# b.net
KiCad netlist of a schematic drawn in EAGLE
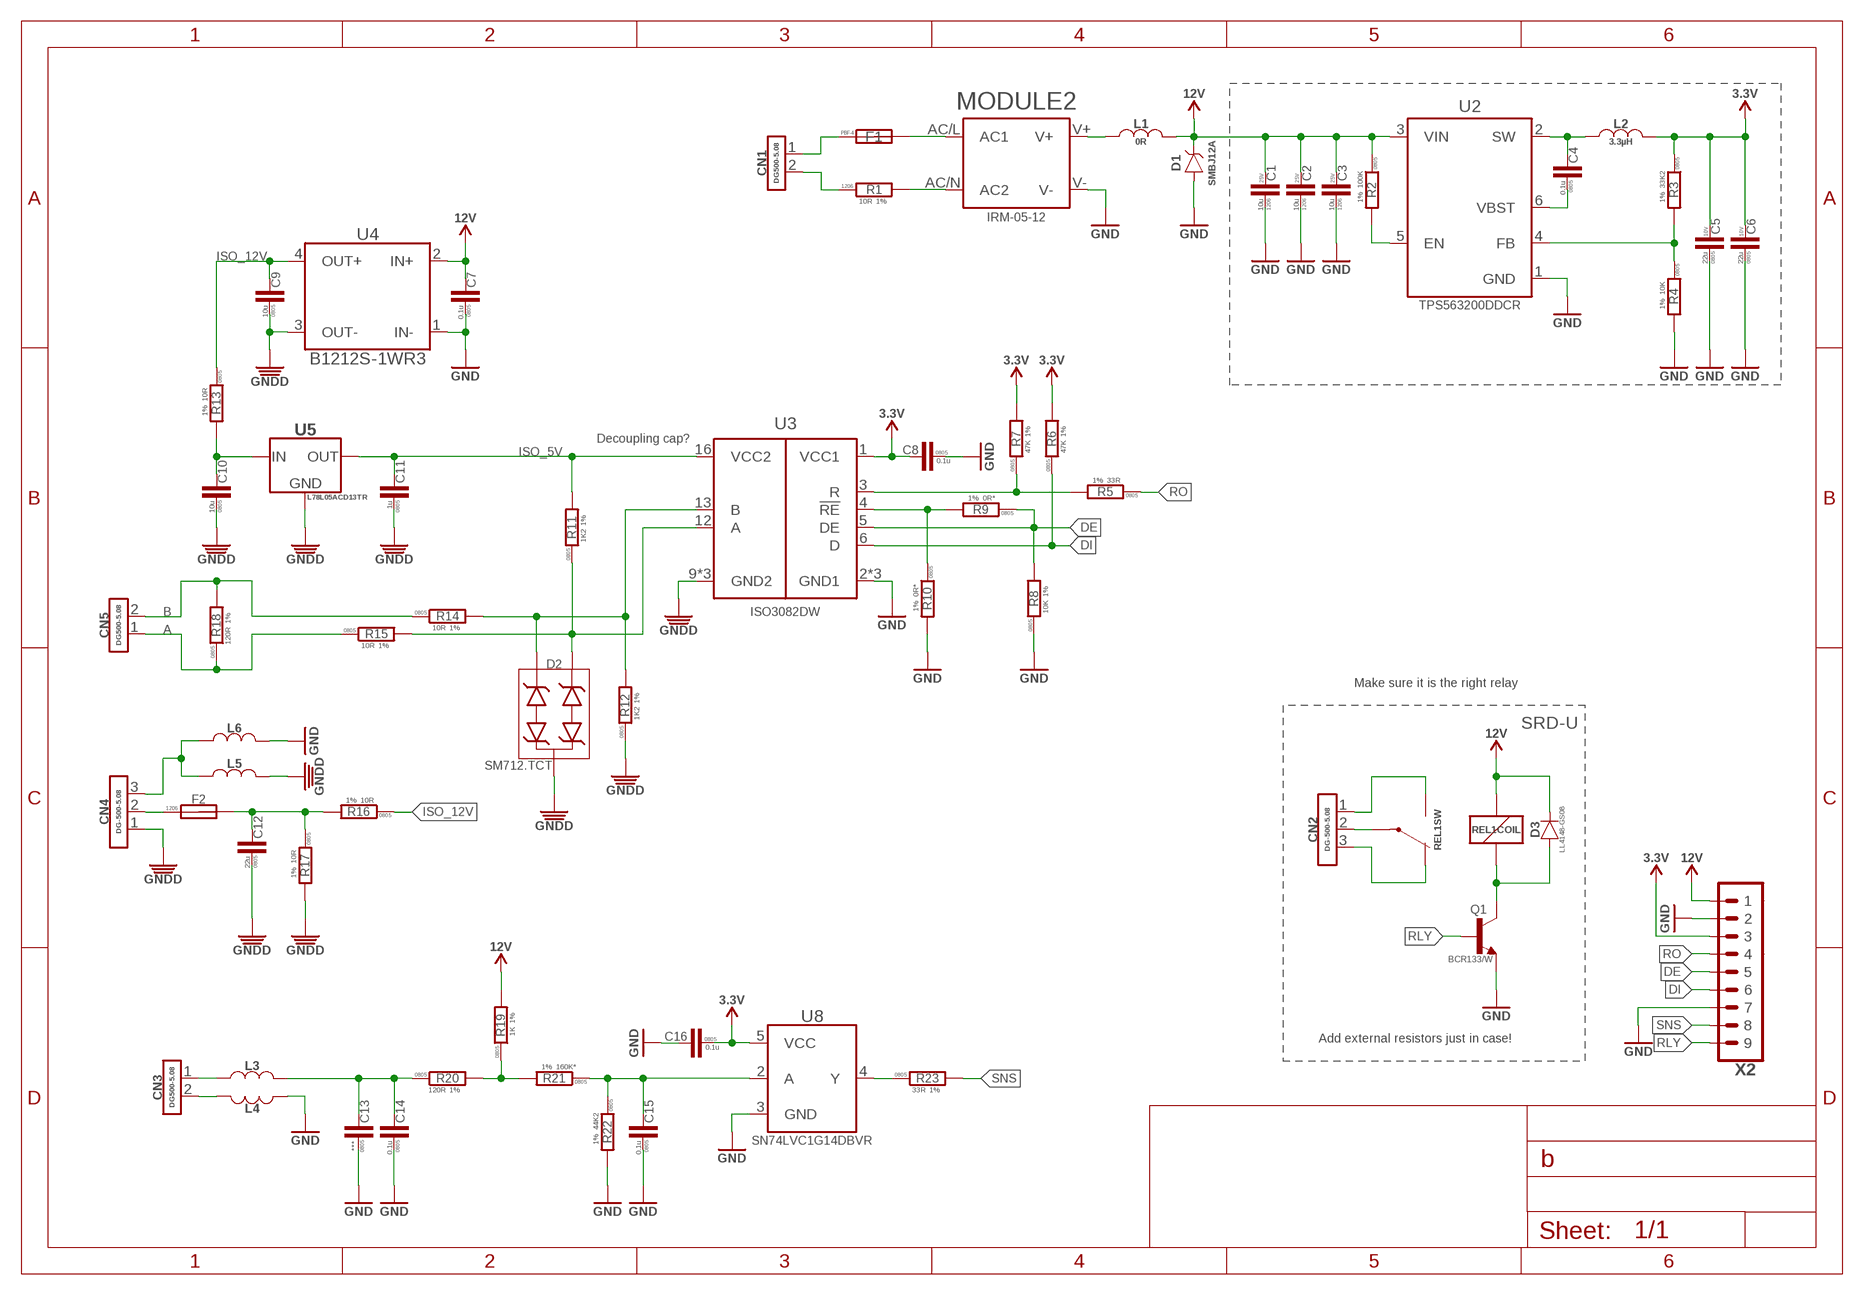
[diagram p0: schematic, sheet 1]

(export (version "E")
  (design (tool "Eeschema 10.0.6"))
  (components
    (comp (ref "C1")
      (value "10u")
      (footprint "eagle-import:C1206")
      (fields (field (name "PACKAGE") "1206") (field (name "VOLTAGE") "25V"))
      (libsource (lib "eagle-import") (part "C-1206"))
    )
    (comp (ref "C2")
      (value "10u")
      (footprint "eagle-import:C1206")
      (fields (field (name "PACKAGE") "1206") (field (name "VOLTAGE") "25V"))
      (libsource (lib "eagle-import") (part "C-1206"))
    )
    (comp (ref "C3")
      (value "10u")
      (footprint "eagle-import:C1206")
      (fields (field (name "PACKAGE") "1206") (field (name "VOLTAGE") "25V"))
      (libsource (lib "eagle-import") (part "C-1206"))
    )
    (comp (ref "C4")
      (value "0.1u")
      (footprint "eagle-import:C0805")
      (fields (field (name "PACKAGE") "0805"))
      (libsource (lib "eagle-import") (part "C-0805"))
    )
    (comp (ref "C5")
      (value "22u")
      (footprint "eagle-import:C0805")
      (fields (field (name "PACKAGE") "0805") (field (name "VOLTAGE") "10V"))
      (libsource (lib "eagle-import") (part "C-0805"))
    )
    (comp (ref "C6")
      (value "22u")
      (footprint "eagle-import:C0805")
      (fields (field (name "PACKAGE") "0805") (field (name "VOLTAGE") "10V"))
      (libsource (lib "eagle-import") (part "C-0805"))
    )
    (comp (ref "C7")
      (value "0.1u")
      (footprint "eagle-import:C0805")
      (fields (field (name "PACKAGE") "0805"))
      (libsource (lib "eagle-import") (part "C-0805"))
    )
    (comp (ref "C8")
      (value "0.1u")
      (footprint "eagle-import:C0805")
      (fields (field (name "PACKAGE") "0805"))
      (libsource (lib "eagle-import") (part "C-0805"))
    )
    (comp (ref "C9")
      (value "10u")
      (footprint "eagle-import:C0805")
      (fields (field (name "PACKAGE") "0805"))
      (libsource (lib "eagle-import") (part "C-0805"))
    )
    (comp (ref "C10")
      (value "10u")
      (footprint "eagle-import:C0805")
      (fields (field (name "PACKAGE") "0805"))
      (libsource (lib "eagle-import") (part "C-0805"))
    )
    (comp (ref "C11")
      (value "1u")
      (footprint "eagle-import:C0805")
      (fields (field (name "PACKAGE") "0805"))
      (libsource (lib "eagle-import") (part "C-0805"))
    )
    (comp (ref "C12")
      (value "22u")
      (footprint "eagle-import:C0805")
      (fields (field (name "PACKAGE") "0805"))
      (libsource (lib "eagle-import") (part "C-0805"))
    )
    (comp (ref "C13")
      (value "***")
      (footprint "eagle-import:C0805")
      (fields (field (name "PACKAGE") "0805"))
      (libsource (lib "eagle-import") (part "C-0805"))
    )
    (comp (ref "C14")
      (value "0.1u")
      (footprint "eagle-import:C0805")
      (fields (field (name "PACKAGE") "0805"))
      (libsource (lib "eagle-import") (part "C-0805"))
    )
    (comp (ref "C15")
      (value "0.1u")
      (footprint "eagle-import:C0805")
      (fields (field (name "PACKAGE") "0805"))
      (libsource (lib "eagle-import") (part "C-0805"))
    )
    (comp (ref "C16")
      (value "0.1u")
      (footprint "eagle-import:C0805")
      (fields (field (name "PACKAGE") "0805"))
      (libsource (lib "eagle-import") (part "C-0805"))
    )
    (comp (ref "CN1")
      (value "CON-2P-DG500-5.08")
      (footprint "eagle-import:DG500-5.08-02P")
      (fields (field (name "TYPE") "DG500-5.08") (field (name "MANF") "Degson Electronics"))
      (libsource (lib "eagle-import") (part "CON-2P-DG500-5.08"))
    )
    (comp (ref "CN2")
      (value "CON-3P-DG500-5.08")
      (footprint "eagle-import:DG500-5.08-03P")
      (fields (field (name "TYPE") "DG-500-5.08") (field (name "MANF") "Degson Electronics"))
      (libsource (lib "eagle-import") (part "CON-3P-DG500-5.08"))
    )
    (comp (ref "CN3")
      (value "CON-2P-DG500-5.08")
      (footprint "eagle-import:DG500-5.08-02P")
      (fields (field (name "TYPE") "DG500-5.08") (field (name "MANF") "Degson Electronics"))
      (libsource (lib "eagle-import") (part "CON-2P-DG500-5.08"))
    )
    (comp (ref "CN4")
      (value "CON-3P-DG500-5.08")
      (footprint "eagle-import:DG500-5.08-03P")
      (fields (field (name "TYPE") "DG-500-5.08") (field (name "MANF") "Degson Electronics"))
      (libsource (lib "eagle-import") (part "CON-3P-DG500-5.08"))
    )
    (comp (ref "CN5")
      (value "CON-2P-DG500-5.08")
      (footprint "eagle-import:DG500-5.08-02P")
      (fields (field (name "TYPE") "DG500-5.08") (field (name "MANF") "Degson Electronics"))
      (libsource (lib "eagle-import") (part "CON-2P-DG500-5.08"))
    )
    (comp (ref "D1")
      (value "SMBJ12A-SMB")
      (footprint "eagle-import:DO-214AA(SMB)")
      (fields (field (name "MANF#") "SMBJ12A") (field (name "MANF") "Littelfuse"))
      (libsource (lib "eagle-import") (part "SMBJ12A-SMB"))
    )
    (comp (ref "D2")
      (value "SM712")
      (footprint "eagle-import:SOT23B-3")
      (fields (field (name "MANF#") "SM712.TCT") (field (name "MANF") "Semtech Corporation"))
      (libsource (lib "eagle-import") (part "SM712"))
    )
    (comp (ref "D3")
      (value "LL4148")
      (footprint "eagle-import:LL-34")
      (fields (field (name "MANF#") "LL4148-GS08") (field (name "MANF") "VISHAY INTERTECHNOLOGY INC"))
      (libsource (lib "eagle-import") (part "LL4148"))
    )
    (comp (ref "F1")
      (value "1.6A")
      (footprint "eagle-import:MST-FUSE")
      (fields
        (field (name "PACKAGE") "1206")
        (field (name "MANF") "Multicomp")
        (field (name "PACKAGE_1") "PBF-4")
      )
      (libsource (lib "eagle-import") (part "FUSE-MST"))
    )
    (comp (ref "F2")
      (value "MF-NSMF050-2")
      (footprint "eagle-import:F1206")
      (fields (field (name "PACKAGE") "1206") (field (name "MANF") "Bourns"))
      (libsource (lib "eagle-import") (part "FUSE-1206"))
    )
    (comp (ref "L1")
      (value "0R")
      (footprint "eagle-import:L0805")
      (libsource (lib "eagle-import") (part "L-0805"))
    )
    (comp (ref "L2")
      (value "3.3µH")
      (footprint "eagle-import:VLS6045EX")
      (fields (field (name "MANF") "TDK Corporation"))
      (libsource (lib "eagle-import") (part "3.3µH-VLS6045EX"))
    )
    (comp (ref "L3")
      (value "L-0805")
      (footprint "eagle-import:L0805")
      (libsource (lib "eagle-import") (part "L-0805"))
    )
    (comp (ref "L4")
      (value "L-0805")
      (footprint "eagle-import:L0805")
      (libsource (lib "eagle-import") (part "L-0805"))
    )
    (comp (ref "L5")
      (value "L-0805")
      (footprint "eagle-import:L0805")
      (libsource (lib "eagle-import") (part "L-0805"))
    )
    (comp (ref "L6")
      (value "L-0805")
      (footprint "eagle-import:L0805")
      (libsource (lib "eagle-import") (part "L-0805"))
    )
    (comp (ref "MODULE2")
      (value "IRM-05-12")
      (footprint "eagle-import:IRM-05")
      (fields (field (name "MANF#") "IRM-05-12") (field (name "MANF") "Meanwell"))
      (libsource (lib "eagle-import") (part "IRM-05-12"))
    )
    (comp (ref "Q1")
      (value "BCR133")
      (footprint "eagle-import:SOT23B-3")
      (fields (field (name "MANF#") "BCR133/W") (field (name "MANF") "INFINEON TECHNOLOGIES AG."))
      (libsource (lib "eagle-import") (part "BCR133"))
    )
    (comp (ref "R1")
      (value "10R")
      (footprint "eagle-import:R1206")
      (fields (field (name "PACKAGE") "1206") (field (name "TOLERANCE") "1%"))
      (libsource (lib "eagle-import") (part "R-1206-1%"))
    )
    (comp (ref "R2")
      (value "100K")
      (footprint "eagle-import:R0805")
      (fields (field (name "PACKAGE") "0805") (field (name "TOLERANCE") "1%"))
      (libsource (lib "eagle-import") (part "R-0805-1%"))
    )
    (comp (ref "R3")
      (value "33K2")
      (footprint "eagle-import:R0805")
      (fields (field (name "PACKAGE") "0805") (field (name "TOLERANCE") "1%"))
      (libsource (lib "eagle-import") (part "R-0805-1%"))
    )
    (comp (ref "R4")
      (value "10K")
      (footprint "eagle-import:R0805")
      (fields (field (name "PACKAGE") "0805") (field (name "TOLERANCE") "1%"))
      (libsource (lib "eagle-import") (part "R-0805-1%"))
    )
    (comp (ref "R5")
      (value "33R")
      (footprint "eagle-import:R0805")
      (fields (field (name "PACKAGE") "0805") (field (name "TOLERANCE") "1%"))
      (libsource (lib "eagle-import") (part "R-0805-1%"))
    )
    (comp (ref "R6")
      (value "47K")
      (footprint "eagle-import:R0805")
      (fields (field (name "PACKAGE") "0805") (field (name "TOLERANCE") "1%"))
      (libsource (lib "eagle-import") (part "R-0805-1%"))
    )
    (comp (ref "R7")
      (value "47K")
      (footprint "eagle-import:R0805")
      (fields (field (name "PACKAGE") "0805") (field (name "TOLERANCE") "1%"))
      (libsource (lib "eagle-import") (part "R-0805-1%"))
    )
    (comp (ref "R8")
      (value "10K")
      (footprint "eagle-import:R0805")
      (fields (field (name "PACKAGE") "0805") (field (name "TOLERANCE") "1%"))
      (libsource (lib "eagle-import") (part "R-0805-1%"))
    )
    (comp (ref "R9")
      (value "0R*")
      (footprint "eagle-import:R0805")
      (fields (field (name "PACKAGE") "0805") (field (name "TOLERANCE") "1%"))
      (libsource (lib "eagle-import") (part "R-0805-1%"))
    )
    (comp (ref "R10")
      (value "0R*")
      (footprint "eagle-import:R0805")
      (fields (field (name "PACKAGE") "0805") (field (name "TOLERANCE") "1%"))
      (libsource (lib "eagle-import") (part "R-0805-1%"))
    )
    (comp (ref "R11")
      (value "1K2")
      (footprint "eagle-import:R0805")
      (fields (field (name "PACKAGE") "0805") (field (name "TOLERANCE") "1%"))
      (libsource (lib "eagle-import") (part "R-0805-1%"))
    )
    (comp (ref "R12")
      (value "1K2")
      (footprint "eagle-import:R0805")
      (fields (field (name "PACKAGE") "0805") (field (name "TOLERANCE") "1%"))
      (libsource (lib "eagle-import") (part "R-0805-1%"))
    )
    (comp (ref "R13")
      (value "10R")
      (footprint "eagle-import:R0805")
      (fields (field (name "PACKAGE") "0805") (field (name "TOLERANCE") "1%"))
      (libsource (lib "eagle-import") (part "R-0805-1%"))
    )
    (comp (ref "R14")
      (value "10R")
      (footprint "eagle-import:R0805")
      (fields (field (name "PACKAGE") "0805") (field (name "TOLERANCE") "1%"))
      (libsource (lib "eagle-import") (part "R-0805-1%"))
    )
    (comp (ref "R15")
      (value "10R")
      (footprint "eagle-import:R0805")
      (fields (field (name "PACKAGE") "0805") (field (name "TOLERANCE") "1%"))
      (libsource (lib "eagle-import") (part "R-0805-1%"))
    )
    (comp (ref "R16")
      (value "10R")
      (footprint "eagle-import:R0805")
      (fields (field (name "PACKAGE") "0805") (field (name "TOLERANCE") "1%"))
      (libsource (lib "eagle-import") (part "R-0805-1%"))
    )
    (comp (ref "R17")
      (value "10R")
      (footprint "eagle-import:R0805")
      (fields (field (name "PACKAGE") "0805") (field (name "TOLERANCE") "1%"))
      (libsource (lib "eagle-import") (part "R-0805-1%"))
    )
    (comp (ref "R18")
      (value "120R")
      (footprint "eagle-import:R0805")
      (fields (field (name "PACKAGE") "0805") (field (name "TOLERANCE") "1%"))
      (libsource (lib "eagle-import") (part "R-0805-1%"))
    )
    (comp (ref "R19")
      (value "1K")
      (footprint "eagle-import:R0805")
      (fields (field (name "PACKAGE") "0805") (field (name "TOLERANCE") "1%"))
      (libsource (lib "eagle-import") (part "R-0805-1%"))
    )
    (comp (ref "R20")
      (value "120R")
      (footprint "eagle-import:R0805")
      (fields (field (name "PACKAGE") "0805") (field (name "TOLERANCE") "1%"))
      (libsource (lib "eagle-import") (part "R-0805-1%"))
    )
    (comp (ref "R21")
      (value "160K*")
      (footprint "eagle-import:R0805")
      (fields (field (name "PACKAGE") "0805") (field (name "TOLERANCE") "1%"))
      (libsource (lib "eagle-import") (part "R-0805-1%"))
    )
    (comp (ref "R22")
      (value "44K2")
      (footprint "eagle-import:R0805")
      (fields (field (name "PACKAGE") "0805") (field (name "TOLERANCE") "1%"))
      (libsource (lib "eagle-import") (part "R-0805-1%"))
    )
    (comp (ref "R23")
      (value "33R")
      (footprint "eagle-import:R0805")
      (fields (field (name "PACKAGE") "0805") (field (name "TOLERANCE") "1%"))
      (libsource (lib "eagle-import") (part "R-0805-1%"))
    )
    (comp (ref "REL1")
      (value "RELAY_SPDTHJR-3FF-SH")
      (footprint "eagle-import:HJR-3FF-12VDC-S-Z")
      (fields
        (field (name "MANF") "Tianbo")
        (field (name "MANF_1") "Xiamen Hongfa Electroacoustic Co.Ltd")
        (field (name "MANF#") "HF3FA/012-ZST")
      )
      (libsource (lib "eagle-import") (part "RELAY_SPDTHJR-3FF-SH"))
    )
    (comp (ref "U2")
      (value "TPS563200")
      (footprint "eagle-import:SOT23-6")
      (fields (field (name "MANF#") "TPS563200DDCR") (field (name "MANF") "Texas Instruments"))
      (libsource (lib "eagle-import") (part "TPS563200"))
    )
    (comp (ref "U3")
      (value "ISO3082")
      (footprint "eagle-import:SO-16W")
      (fields (field (name "MANF#") "ISO3082DW") (field (name "MANF") "Texas Instruments"))
      (libsource (lib "eagle-import") (part "ISO3082"))
    )
    (comp (ref "U4")
      (value "B1212S-1WR3")
      (footprint "eagle-import:SIP-4")
      (fields (field (name "MANF#") "B1212S-1WR3") (field (name "MANF") "Mornsun Power"))
      (libsource (lib "eagle-import") (part "B1212S-1WR3"))
    )
    (comp (ref "U5")
      (value "L78L05ACD13TR")
      (footprint "eagle-import:SOIC8")
      (fields (field (name "MANF#") "L78L05ACD13TR") (field (name "MANF") "STMicroelectronics"))
      (libsource (lib "eagle-import") (part "L78L05ACD13TR"))
    )
    (comp (ref "U8")
      (value "74LVC1G14DBV")
      (footprint "eagle-import:SOT23-5")
      (fields (field (name "MANF#") "SN74LVC1G14DBVR") (field (name "MANF") "Texas Instruments"))
      (libsource (lib "eagle-import") (part "74LVC1G14DBV"))
    )
    (comp (ref "X2")
      (value "PINHEAD_1X09-2.54-TH-MALE")
      (footprint "eagle-import:1X09-PTH-2.54")
      (libsource (lib "eagle-import") (part "PINHEAD_1X09-2.54-TH-MALE"))
    )
  )
  (nets
    (net (code "1") (name "/A") (class "Default")
      (node (ref "CN5") (pin "1") (pinfunction "1_1") (pintype "bidirectional"))
      (node (ref "R15") (pin "1") (pinfunction "1_1") (pintype "passive"))
      (node (ref "R18") (pin "1") (pinfunction "1_1") (pintype "passive"))
    )
    (net (code "2") (name "/B") (class "Default")
      (node (ref "CN5") (pin "2") (pinfunction "2_2") (pintype "bidirectional"))
      (node (ref "R14") (pin "1") (pinfunction "1_1") (pintype "passive"))
      (node (ref "R18") (pin "2") (pinfunction "2_2") (pintype "passive"))
    )
    (net (code "3") (name "/ISO_5V") (class "Default")
      (node (ref "C11") (pin "2") (pinfunction "2_2") (pintype "passive"))
      (node (ref "R11") (pin "2") (pinfunction "2_2") (pintype "passive"))
      (node (ref "U3") (pin "16") (pinfunction "VCC2_16") (pintype "bidirectional"))
      (node (ref "U5") (pin "1") (pinfunction "OUT_1") (pintype "power_in"))
    )
    (net (code "4") (name "3.3V") (class "Default")
      (node (ref "C16") (pin "1") (pinfunction "1_1") (pintype "passive"))
      (node (ref "C5") (pin "2") (pinfunction "2_2") (pintype "passive"))
      (node (ref "C6") (pin "2") (pinfunction "2_2") (pintype "passive"))
      (node (ref "C8") (pin "2") (pinfunction "2_2") (pintype "passive"))
      (node (ref "L2") (pin "P$2") (pinfunction "2_P$2") (pintype "bidirectional"))
      (node (ref "R3") (pin "1") (pinfunction "1_1") (pintype "passive"))
      (node (ref "R6") (pin "2") (pinfunction "2_2") (pintype "passive"))
      (node (ref "R7") (pin "2") (pinfunction "2_2") (pintype "passive"))
      (node (ref "U3") (pin "1") (pinfunction "VCC1_1") (pintype "bidirectional"))
      (node (ref "U8") (pin "5") (pinfunction "VCC_5") (pintype "bidirectional"))
      (node (ref "X2") (pin "3") (pinfunction "3_3") (pintype "passive"))
    )
    (net (code "5") (name "12V") (class "Default")
      (node (ref "C1") (pin "P$2") (pinfunction "2_P$2") (pintype "passive"))
      (node (ref "C2") (pin "P$2") (pinfunction "2_P$2") (pintype "passive"))
      (node (ref "C3") (pin "P$2") (pinfunction "2_P$2") (pintype "passive"))
      (node (ref "C7") (pin "2") (pinfunction "2_2") (pintype "passive"))
      (node (ref "D1") (pin "C") (pinfunction "C_C") (pintype "bidirectional"))
      (node (ref "D3") (pin "C") (pinfunction "C_C") (pintype "passive"))
      (node (ref "L1") (pin "2") (pinfunction "P$2_2") (pintype "bidirectional"))
      (node (ref "R19") (pin "2") (pinfunction "2_2") (pintype "passive"))
      (node (ref "R2") (pin "1") (pinfunction "1_1") (pintype "passive"))
      (node (ref "REL1") (pin "2") (pinfunction "1_2") (pintype "passive"))
      (node (ref "U2") (pin "3") (pinfunction "VIN_3") (pintype "bidirectional"))
      (node (ref "U4") (pin "2") (pinfunction "IN+_2") (pintype "bidirectional"))
      (node (ref "X2") (pin "1") (pinfunction "1_1") (pintype "passive"))
    )
    (net (code "6") (name "DE") (class "Default")
      (node (ref "R8") (pin "2") (pinfunction "2_2") (pintype "passive"))
      (node (ref "R9") (pin "1") (pinfunction "1_1") (pintype "passive"))
      (node (ref "U3") (pin "5") (pinfunction "DE_5") (pintype "bidirectional"))
      (node (ref "X2") (pin "5") (pinfunction "5_5") (pintype "passive"))
    )
    (net (code "7") (name "DI") (class "Default")
      (node (ref "R6") (pin "1") (pinfunction "1_1") (pintype "passive"))
      (node (ref "U3") (pin "6") (pinfunction "D_6") (pintype "bidirectional"))
      (node (ref "X2") (pin "6") (pinfunction "6_6") (pintype "passive"))
    )
    (net (code "8") (name "GND") (class "Default")
      (node (ref "C1") (pin "P$1") (pinfunction "1_P$1") (pintype "passive"))
      (node (ref "C13") (pin "1") (pinfunction "1_1") (pintype "passive"))
      (node (ref "C14") (pin "1") (pinfunction "1_1") (pintype "passive"))
      (node (ref "C15") (pin "1") (pinfunction "1_1") (pintype "passive"))
      (node (ref "C16") (pin "2") (pinfunction "2_2") (pintype "passive"))
      (node (ref "C2") (pin "P$1") (pinfunction "1_P$1") (pintype "passive"))
      (node (ref "C3") (pin "P$1") (pinfunction "1_P$1") (pintype "passive"))
      (node (ref "C5") (pin "1") (pinfunction "1_1") (pintype "passive"))
      (node (ref "C6") (pin "1") (pinfunction "1_1") (pintype "passive"))
      (node (ref "C7") (pin "1") (pinfunction "1_1") (pintype "passive"))
      (node (ref "C8") (pin "1") (pinfunction "1_1") (pintype "passive"))
      (node (ref "D1") (pin "A") (pinfunction "A_A") (pintype "bidirectional"))
      (node (ref "L4") (pin "2") (pinfunction "P$2_2") (pintype "bidirectional"))
      (node (ref "L6") (pin "1") (pinfunction "P$1_1") (pintype "bidirectional"))
      (node (ref "MODULE2") (pin "V-") (pinfunction "V-_V-") (pintype "bidirectional"))
      (node (ref "Q1") (pin "2") (pinfunction "E_2") (pintype "passive"))
      (node (ref "R10") (pin "2") (pinfunction "2_2") (pintype "passive"))
      (node (ref "R22") (pin "2") (pinfunction "2_2") (pintype "passive"))
      (node (ref "R4") (pin "2") (pinfunction "2_2") (pintype "passive"))
      (node (ref "R8") (pin "1") (pinfunction "1_1") (pintype "passive"))
      (node (ref "U2") (pin "1") (pinfunction "GND_1") (pintype "bidirectional"))
      (node (ref "U3") (pin "2") (pinfunction "GND1_2") (pintype "bidirectional"))
      (node (ref "U3") (pin "7") (pinfunction "GND1_7") (pintype "bidirectional"))
      (node (ref "U3") (pin "8") (pinfunction "GND1_8") (pintype "bidirectional"))
      (node (ref "U4") (pin "1") (pinfunction "IN-_1") (pintype "bidirectional"))
      (node (ref "U8") (pin "3") (pinfunction "GND_3") (pintype "bidirectional"))
      (node (ref "X2") (pin "2") (pinfunction "2_2") (pintype "passive"))
      (node (ref "X2") (pin "7") (pinfunction "7_7") (pintype "passive"))
    )
    (net (code "9") (name "GNDD") (class "Default")
      (node (ref "C10") (pin "1") (pinfunction "1_1") (pintype "passive"))
      (node (ref "C11") (pin "1") (pinfunction "1_1") (pintype "passive"))
      (node (ref "C12") (pin "1") (pinfunction "1_1") (pintype "passive"))
      (node (ref "C9") (pin "1") (pinfunction "1_1") (pintype "passive"))
      (node (ref "CN4") (pin "1") (pinfunction "1_1") (pintype "bidirectional"))
      (node (ref "D2") (pin "3") (pinfunction "P$1_3") (pintype "bidirectional"))
      (node (ref "L5") (pin "2") (pinfunction "P$2_2") (pintype "bidirectional"))
      (node (ref "R12") (pin "1") (pinfunction "1_1") (pintype "passive"))
      (node (ref "R17") (pin "2") (pinfunction "2_2") (pintype "passive"))
      (node (ref "U3") (pin "10") (pinfunction "GND2_10") (pintype "bidirectional"))
      (node (ref "U3") (pin "15") (pinfunction "GND2_15") (pintype "bidirectional"))
      (node (ref "U3") (pin "9") (pinfunction "GND2_9") (pintype "bidirectional"))
      (node (ref "U4") (pin "3") (pinfunction "OUT-_3") (pintype "bidirectional"))
      (node (ref "U5") (pin "2") (pinfunction "GND_2") (pintype "power_in"))
      (node (ref "U5") (pin "3") (pinfunction "GND_3") (pintype "power_in"))
      (node (ref "U5") (pin "6") (pinfunction "GND_6") (pintype "power_in"))
      (node (ref "U5") (pin "7") (pinfunction "GND_7") (pintype "power_in"))
    )
    (net (code "10") (name "ISO_12V") (class "Default")
      (node (ref "C9") (pin "2") (pinfunction "2_2") (pintype "passive"))
      (node (ref "R13") (pin "1") (pinfunction "1_1") (pintype "passive"))
      (node (ref "R16") (pin "1") (pinfunction "1_1") (pintype "passive"))
      (node (ref "U4") (pin "4") (pinfunction "OUT+_4") (pintype "bidirectional"))
    )
    (net (code "11") (name "Net-(CN1-Pad1)") (class "Default")
      (node (ref "CN1") (pin "1") (pinfunction "1_1") (pintype "bidirectional"))
      (node (ref "F1") (pin "1") (pinfunction "1_1") (pintype "passive"))
    )
    (net (code "12") (name "Net-(D2-C2)") (class "Default")
      (node (ref "D2") (pin "2") (pinfunction "C2_2") (pintype "bidirectional"))
      (node (ref "R11") (pin "1") (pinfunction "1_1") (pintype "passive"))
      (node (ref "R15") (pin "2") (pinfunction "2_2") (pintype "passive"))
      (node (ref "U3") (pin "12") (pinfunction "A_12") (pintype "bidirectional"))
    )
    (net (code "13") (name "Net-(D2-C3)") (class "Default")
      (node (ref "D2") (pin "1") (pinfunction "C3_1") (pintype "bidirectional"))
      (node (ref "R12") (pin "2") (pinfunction "2_2") (pintype "passive"))
      (node (ref "R14") (pin "2") (pinfunction "2_2") (pintype "passive"))
      (node (ref "U3") (pin "13") (pinfunction "B_13") (pintype "bidirectional"))
    )
    (net (code "14") (name "Net-(F2-1)") (class "Default")
      (node (ref "CN4") (pin "2") (pinfunction "2_2") (pintype "bidirectional"))
      (node (ref "F2") (pin "P$1") (pinfunction "1_P$1") (pintype "passive"))
    )
    (net (code "15") (name "Net-(F2-2)") (class "Default")
      (node (ref "C12") (pin "2") (pinfunction "2_2") (pintype "passive"))
      (node (ref "F2") (pin "P$2") (pinfunction "2_P$2") (pintype "passive"))
      (node (ref "R16") (pin "2") (pinfunction "2_2") (pintype "passive"))
      (node (ref "R17") (pin "1") (pinfunction "1_1") (pintype "passive"))
    )
    (net (code "16") (name "Net-(L1-P$1)") (class "Default")
      (node (ref "L1") (pin "1") (pinfunction "P$1_1") (pintype "bidirectional"))
      (node (ref "MODULE2") (pin "V+") (pinfunction "V+_V+") (pintype "bidirectional"))
    )
    (net (code "17") (name "Net-(L2-1)") (class "Default")
      (node (ref "C4") (pin "2") (pinfunction "2_2") (pintype "passive"))
      (node (ref "L2") (pin "P$1") (pinfunction "1_P$1") (pintype "bidirectional"))
      (node (ref "U2") (pin "2") (pinfunction "SW_2") (pintype "bidirectional"))
    )
    (net (code "18") (name "Net-(L3-P$1)") (class "Default")
      (node (ref "CN3") (pin "1") (pinfunction "1_1") (pintype "bidirectional"))
      (node (ref "L3") (pin "1") (pinfunction "P$1_1") (pintype "bidirectional"))
    )
    (net (code "19") (name "Net-(L3-P$2)") (class "Default")
      (node (ref "C13") (pin "2") (pinfunction "2_2") (pintype "passive"))
      (node (ref "C14") (pin "2") (pinfunction "2_2") (pintype "passive"))
      (node (ref "L3") (pin "2") (pinfunction "P$2_2") (pintype "bidirectional"))
      (node (ref "R20") (pin "1") (pinfunction "1_1") (pintype "passive"))
    )
    (net (code "20") (name "Net-(L4-P$1)") (class "Default")
      (node (ref "CN3") (pin "2") (pinfunction "2_2") (pintype "bidirectional"))
      (node (ref "L4") (pin "1") (pinfunction "P$1_1") (pintype "bidirectional"))
    )
    (net (code "21") (name "Net-(L5-P$1)") (class "Default")
      (node (ref "CN4") (pin "3") (pinfunction "3_3") (pintype "bidirectional"))
      (node (ref "L5") (pin "1") (pinfunction "P$1_1") (pintype "bidirectional"))
      (node (ref "L6") (pin "2") (pinfunction "P$2_2") (pintype "bidirectional"))
    )
    (net (code "22") (name "Net-(MODULE2-AC1)") (class "Default")
      (node (ref "F1") (pin "2") (pinfunction "2_2") (pintype "passive"))
      (node (ref "MODULE2") (pin "AC/L") (pinfunction "AC1_AC/L") (pintype "bidirectional"))
    )
    (net (code "23") (name "Net-(MODULE2-AC2)") (class "Default")
      (node (ref "MODULE2") (pin "AC/N") (pinfunction "AC2_AC/N") (pintype "bidirectional"))
      (node (ref "R1") (pin "P$2") (pinfunction "2_P$2") (pintype "passive"))
    )
    (net (code "24") (name "Net-(Q1-C)") (class "Default")
      (node (ref "D3") (pin "A") (pinfunction "A_A") (pintype "passive"))
      (node (ref "Q1") (pin "3") (pinfunction "C_3") (pintype "passive"))
      (node (ref "REL1") (pin "5") (pinfunction "2_5") (pintype "passive"))
    )
    (net (code "25") (name "Net-(R1-1)") (class "Default")
      (node (ref "CN1") (pin "2") (pinfunction "2_2") (pintype "bidirectional"))
      (node (ref "R1") (pin "P$1") (pinfunction "1_P$1") (pintype "passive"))
    )
    (net (code "26") (name "Net-(R19-Pad1)") (class "Default")
      (node (ref "R19") (pin "1") (pinfunction "1_1") (pintype "passive"))
      (node (ref "R20") (pin "2") (pinfunction "2_2") (pintype "passive"))
      (node (ref "R21") (pin "2") (pinfunction "2_2") (pintype "passive"))
    )
    (net (code "27") (name "Net-(REL1B-COM)") (class "Default")
      (node (ref "CN2") (pin "2") (pinfunction "2_2") (pintype "bidirectional"))
      (node (ref "REL1") (pin "1") (pinfunction "COM_1") (pintype "passive"))
    )
    (net (code "28") (name "Net-(REL1B-NC)") (class "Default")
      (node (ref "CN2") (pin "3") (pinfunction "3_3") (pintype "bidirectional"))
      (node (ref "REL1") (pin "4") (pinfunction "NC_4") (pintype "passive"))
    )
    (net (code "29") (name "Net-(REL1B-NO)") (class "Default")
      (node (ref "CN2") (pin "1") (pinfunction "1_1") (pintype "bidirectional"))
      (node (ref "REL1") (pin "3") (pinfunction "NO_3") (pintype "passive"))
    )
    (net (code "30") (name "Net-(U2-EN)") (class "Default")
      (node (ref "R2") (pin "2") (pinfunction "2_2") (pintype "passive"))
      (node (ref "U2") (pin "5") (pinfunction "EN_5") (pintype "bidirectional"))
    )
    (net (code "31") (name "Net-(U2-FB)") (class "Default")
      (node (ref "R3") (pin "2") (pinfunction "2_2") (pintype "passive"))
      (node (ref "R4") (pin "1") (pinfunction "1_1") (pintype "passive"))
      (node (ref "U2") (pin "4") (pinfunction "FB_4") (pintype "bidirectional"))
    )
    (net (code "32") (name "Net-(U2-VBST)") (class "Default")
      (node (ref "C4") (pin "1") (pinfunction "1_1") (pintype "passive"))
      (node (ref "U2") (pin "6") (pinfunction "VBST_6") (pintype "bidirectional"))
    )
    (net (code "33") (name "Net-(U3-R)") (class "Default")
      (node (ref "R5") (pin "2") (pinfunction "2_2") (pintype "passive"))
      (node (ref "R7") (pin "1") (pinfunction "1_1") (pintype "passive"))
      (node (ref "U3") (pin "3") (pinfunction "R_3") (pintype "bidirectional"))
    )
    (net (code "34") (name "Net-(U3-~{RE})") (class "Default")
      (node (ref "R10") (pin "1") (pinfunction "1_1") (pintype "passive"))
      (node (ref "R9") (pin "2") (pinfunction "2_2") (pintype "passive"))
      (node (ref "U3") (pin "4") (pinfunction "~{RE}_4") (pintype "bidirectional"))
    )
    (net (code "35") (name "Net-(U5-IN)") (class "Default")
      (node (ref "C10") (pin "2") (pinfunction "2_2") (pintype "passive"))
      (node (ref "R13") (pin "2") (pinfunction "2_2") (pintype "passive"))
      (node (ref "U5") (pin "8") (pinfunction "IN_8") (pintype "power_in"))
    )
    (net (code "36") (name "Net-(U8-A)") (class "Default")
      (node (ref "C15") (pin "2") (pinfunction "2_2") (pintype "passive"))
      (node (ref "R21") (pin "1") (pinfunction "1_1") (pintype "passive"))
      (node (ref "R22") (pin "1") (pinfunction "1_1") (pintype "passive"))
      (node (ref "U8") (pin "2") (pinfunction "A_2") (pintype "bidirectional"))
    )
    (net (code "37") (name "Net-(U8-Y)") (class "Default")
      (node (ref "R23") (pin "1") (pinfunction "1_1") (pintype "passive"))
      (node (ref "U8") (pin "4") (pinfunction "Y_4") (pintype "bidirectional"))
    )
    (net (code "38") (name "RLY") (class "Default")
      (node (ref "Q1") (pin "1") (pinfunction "B_1") (pintype "passive"))
      (node (ref "X2") (pin "9") (pinfunction "9_9") (pintype "passive"))
    )
    (net (code "39") (name "RO") (class "Default")
      (node (ref "R5") (pin "1") (pinfunction "1_1") (pintype "passive"))
      (node (ref "X2") (pin "4") (pinfunction "4_4") (pintype "passive"))
    )
    (net (code "40") (name "SNS") (class "Default")
      (node (ref "R23") (pin "2") (pinfunction "2_2") (pintype "passive"))
      (node (ref "X2") (pin "8") (pinfunction "8_8") (pintype "passive"))
    )
  )
)
